# PCF8575_Shield.net
KiCad netlist of a schematic drawn in EAGLE
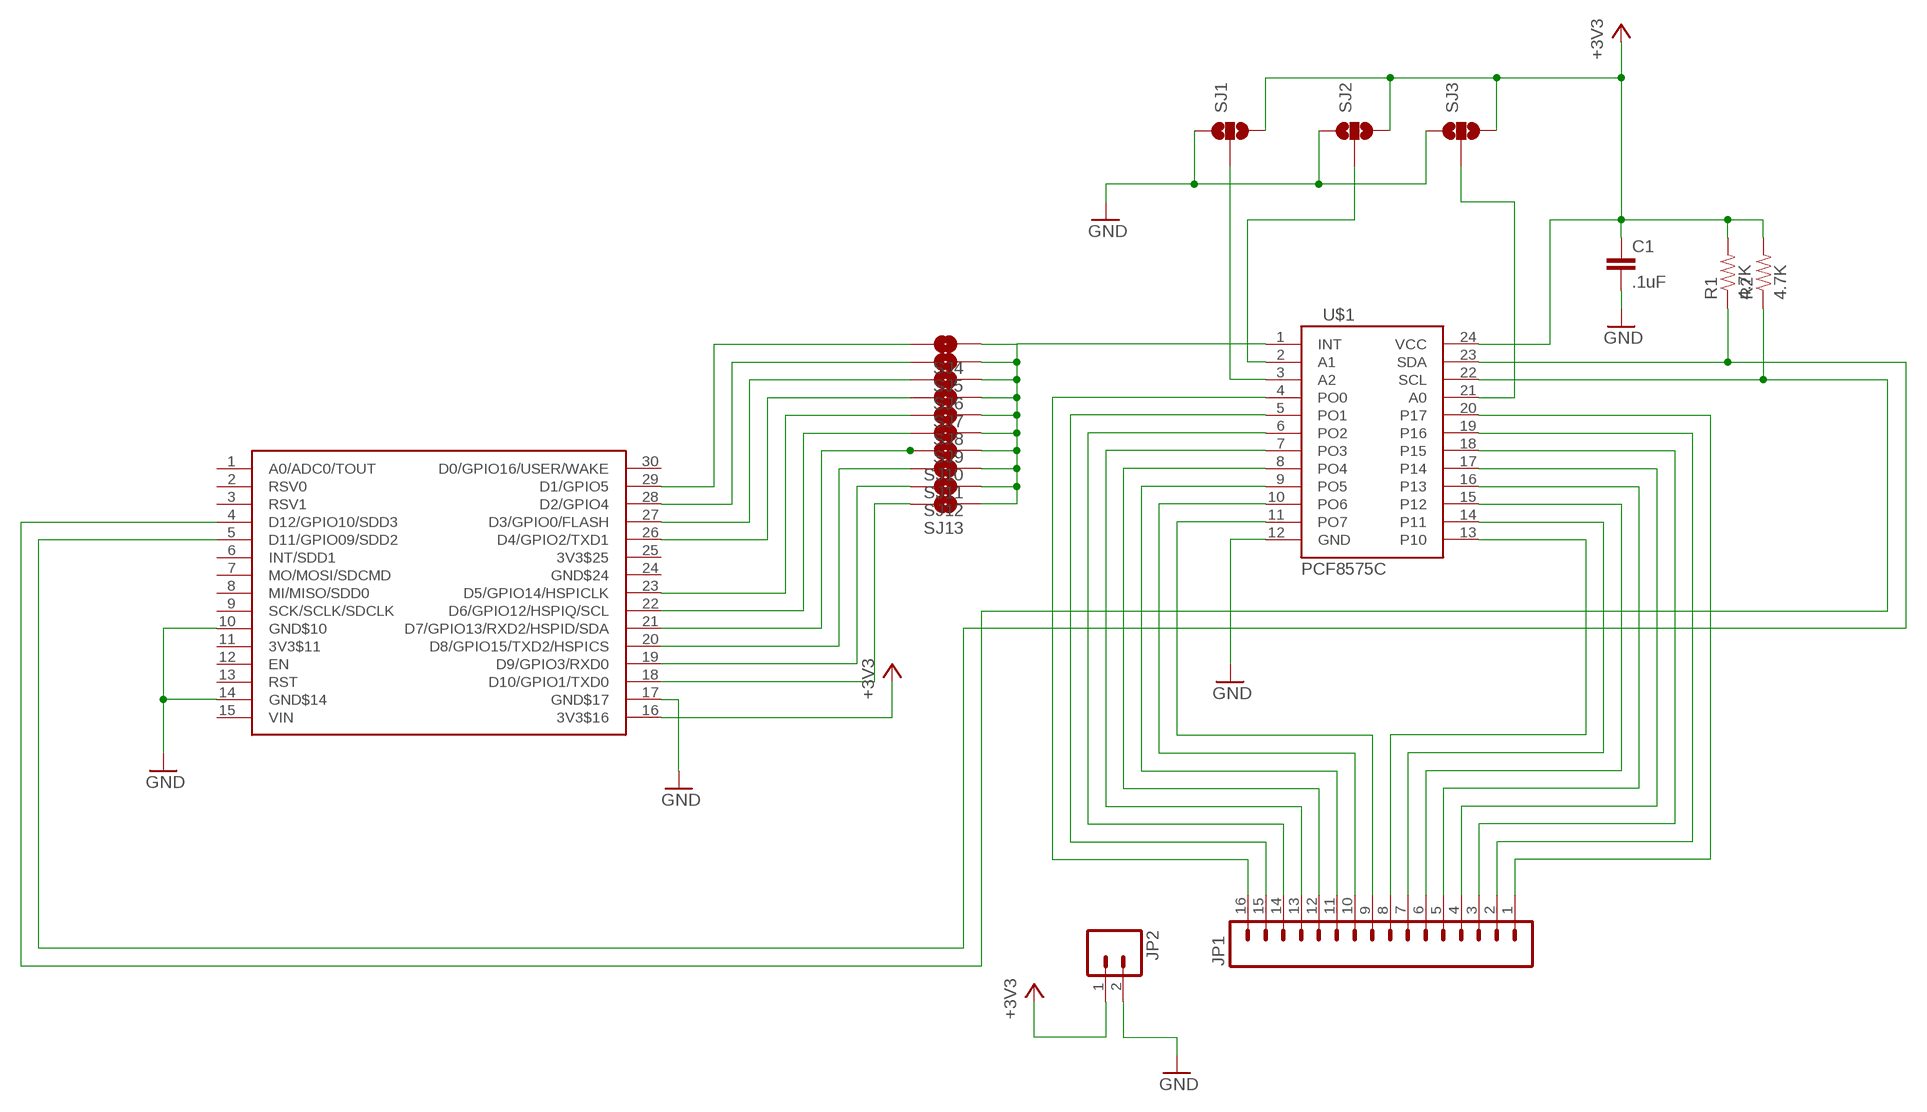
[diagram p0: schematic, sheet 1]

(export (version "E")
  (design (tool "Eeschema 10.0.6"))
  (components
    (comp (ref "C1")
      (value ".1uF")
      (footprint "eagle-import:0603-CAP")
      (libsource (lib "eagle-import") (part "CAP0603-CAP"))
    )
    (comp (ref "JP1")
      (value "M161X16_NO_SILK")
      (footprint "eagle-import:1X16_NO_SILK")
      (libsource (lib "eagle-import") (part "M161X16_NO_SILK"))
    )
    (comp (ref "JP2")
      (value "M02PTH")
      (footprint "eagle-import:1X02")
      (libsource (lib "eagle-import") (part "M02PTH"))
    )
    (comp (ref "R1")
      (value "4.7K")
      (footprint "eagle-import:0603-RES")
      (libsource (lib "eagle-import") (part "RESISTOR0603-RES"))
    )
    (comp (ref "R2")
      (value "4.7K")
      (footprint "eagle-import:0603-RES")
      (libsource (lib "eagle-import") (part "RESISTOR0603-RES"))
    )
    (comp (ref "SJ1")
      (value "SOLDERJUMPER_2WAYPASTE1&2")
      (footprint "eagle-import:SJ_3_PASTE1&2")
      (libsource (lib "eagle-import") (part "SOLDERJUMPER_2WAYPASTE1&2"))
    )
    (comp (ref "SJ2")
      (value "SOLDERJUMPER_2WAYPASTE1&2")
      (footprint "eagle-import:SJ_3_PASTE1&2")
      (libsource (lib "eagle-import") (part "SOLDERJUMPER_2WAYPASTE1&2"))
    )
    (comp (ref "SJ3")
      (value "SOLDERJUMPER_2WAYPASTE1&2")
      (footprint "eagle-import:SJ_3_PASTE1&2")
      (libsource (lib "eagle-import") (part "SOLDERJUMPER_2WAYPASTE1&2"))
    )
    (comp (ref "SJ4")
      (value "SOLDERJUMPERNO")
      (footprint "eagle-import:SJ_2S-NO")
      (libsource (lib "eagle-import") (part "SOLDERJUMPERNO"))
    )
    (comp (ref "SJ5")
      (value "SOLDERJUMPERNO")
      (footprint "eagle-import:SJ_2S-NO")
      (libsource (lib "eagle-import") (part "SOLDERJUMPERNO"))
    )
    (comp (ref "SJ6")
      (value "SOLDERJUMPERNO")
      (footprint "eagle-import:SJ_2S-NO")
      (libsource (lib "eagle-import") (part "SOLDERJUMPERNO"))
    )
    (comp (ref "SJ7")
      (value "SOLDERJUMPERNO")
      (footprint "eagle-import:SJ_2S-NO")
      (libsource (lib "eagle-import") (part "SOLDERJUMPERNO"))
    )
    (comp (ref "SJ8")
      (value "SOLDERJUMPERNO")
      (footprint "eagle-import:SJ_2S-NO")
      (libsource (lib "eagle-import") (part "SOLDERJUMPERNO"))
    )
    (comp (ref "SJ9")
      (value "SOLDERJUMPERNO")
      (footprint "eagle-import:SJ_2S-NO")
      (libsource (lib "eagle-import") (part "SOLDERJUMPERNO"))
    )
    (comp (ref "SJ10")
      (value "SOLDERJUMPERNO")
      (footprint "eagle-import:SJ_2S-NO")
      (libsource (lib "eagle-import") (part "SOLDERJUMPERNO"))
    )
    (comp (ref "SJ11")
      (value "SOLDERJUMPERNO")
      (footprint "eagle-import:SJ_2S-NO")
      (libsource (lib "eagle-import") (part "SOLDERJUMPERNO"))
    )
    (comp (ref "SJ12")
      (value "SOLDERJUMPERNO")
      (footprint "eagle-import:SJ_2S-NO")
      (libsource (lib "eagle-import") (part "SOLDERJUMPERNO"))
    )
    (comp (ref "SJ13")
      (value "SOLDERJUMPERNO")
      (footprint "eagle-import:SJ_2S-NO")
      (libsource (lib "eagle-import") (part "SOLDERJUMPERNO"))
    )
    (comp (ref "U$1")
      (value "PCF8575C")
      (footprint "eagle-import:SO-24DW")
      (libsource (lib "eagle-import") (part "PCF8575C"))
    )
    (comp (ref "U$2")
      (value "NERDSHIELD")
      (footprint "eagle-import:NERDUINO_STACK")
      (libsource (lib "eagle-import") (part "NERDSHIELD"))
    )
  )
  (nets
    (net (code "1") (name "+3V3") (class "Default")
      (node (ref "C1") (pin "1") (pinfunction "1_1") (pintype "passive"))
      (node (ref "JP2") (pin "1") (pinfunction "1_1") (pintype "passive"))
      (node (ref "R1") (pin "2") (pinfunction "2_2") (pintype "passive"))
      (node (ref "R2") (pin "2") (pinfunction "2_2") (pintype "passive"))
      (node (ref "SJ1") (pin "3") (pinfunction "3_3") (pintype "passive"))
      (node (ref "SJ2") (pin "3") (pinfunction "3_3") (pintype "passive"))
      (node (ref "SJ3") (pin "3") (pinfunction "3_3") (pintype "passive"))
      (node (ref "U$1") (pin "24") (pinfunction "VCC_24") (pintype "bidirectional"))
      (node (ref "U$2") (pin "16") (pinfunction "3V3$16_16") (pintype "bidirectional"))
    )
    (net (code "2") (name "GND") (class "Default")
      (node (ref "C1") (pin "2") (pinfunction "2_2") (pintype "passive"))
      (node (ref "JP2") (pin "2") (pinfunction "2_2") (pintype "passive"))
      (node (ref "SJ1") (pin "1") (pinfunction "1_1") (pintype "passive"))
      (node (ref "SJ2") (pin "1") (pinfunction "1_1") (pintype "passive"))
      (node (ref "SJ3") (pin "1") (pinfunction "1_1") (pintype "passive"))
      (node (ref "U$1") (pin "12") (pinfunction "GND_12") (pintype "bidirectional"))
      (node (ref "U$2") (pin "10") (pinfunction "GND$10_10") (pintype "bidirectional"))
      (node (ref "U$2") (pin "14") (pinfunction "GND$14_14") (pintype "bidirectional"))
      (node (ref "U$2") (pin "17") (pinfunction "GND$17_17") (pintype "bidirectional"))
    )
    (net (code "3") (name "Net-(U$1-A0)") (class "Default")
      (node (ref "SJ3") (pin "2") (pinfunction "2_2") (pintype "passive"))
      (node (ref "U$1") (pin "21") (pinfunction "A0_21") (pintype "bidirectional"))
    )
    (net (code "4") (name "Net-(U$1-A1)") (class "Default")
      (node (ref "SJ2") (pin "2") (pinfunction "2_2") (pintype "passive"))
      (node (ref "U$1") (pin "2") (pinfunction "A1_2") (pintype "bidirectional"))
    )
    (net (code "5") (name "Net-(U$1-A2)") (class "Default")
      (node (ref "SJ1") (pin "2") (pinfunction "2_2") (pintype "passive"))
      (node (ref "U$1") (pin "3") (pinfunction "A2_3") (pintype "bidirectional"))
    )
    (net (code "6") (name "Net-(U$1-INT)") (class "Default")
      (node (ref "SJ10") (pin "1") (pinfunction "1_1") (pintype "passive"))
      (node (ref "SJ11") (pin "1") (pinfunction "1_1") (pintype "passive"))
      (node (ref "SJ12") (pin "1") (pinfunction "1_1") (pintype "passive"))
      (node (ref "SJ13") (pin "1") (pinfunction "1_1") (pintype "passive"))
      (node (ref "SJ4") (pin "1") (pinfunction "1_1") (pintype "passive"))
      (node (ref "SJ5") (pin "1") (pinfunction "1_1") (pintype "passive"))
      (node (ref "SJ6") (pin "1") (pinfunction "1_1") (pintype "passive"))
      (node (ref "SJ7") (pin "1") (pinfunction "1_1") (pintype "passive"))
      (node (ref "SJ8") (pin "1") (pinfunction "1_1") (pintype "passive"))
      (node (ref "SJ9") (pin "1") (pinfunction "1_1") (pintype "passive"))
      (node (ref "U$1") (pin "1") (pinfunction "INT_1") (pintype "bidirectional"))
    )
    (net (code "7") (name "Net-(U$1-P10)") (class "Default")
      (node (ref "JP1") (pin "8") (pinfunction "8_8") (pintype "passive"))
      (node (ref "U$1") (pin "13") (pinfunction "P10_13") (pintype "bidirectional"))
    )
    (net (code "8") (name "Net-(U$1-P11)") (class "Default")
      (node (ref "JP1") (pin "7") (pinfunction "7_7") (pintype "passive"))
      (node (ref "U$1") (pin "14") (pinfunction "P11_14") (pintype "bidirectional"))
    )
    (net (code "9") (name "Net-(U$1-P12)") (class "Default")
      (node (ref "JP1") (pin "6") (pinfunction "6_6") (pintype "passive"))
      (node (ref "U$1") (pin "15") (pinfunction "P12_15") (pintype "bidirectional"))
    )
    (net (code "10") (name "Net-(U$1-P13)") (class "Default")
      (node (ref "JP1") (pin "5") (pinfunction "5_5") (pintype "passive"))
      (node (ref "U$1") (pin "16") (pinfunction "P13_16") (pintype "bidirectional"))
    )
    (net (code "11") (name "Net-(U$1-P14)") (class "Default")
      (node (ref "JP1") (pin "4") (pinfunction "4_4") (pintype "passive"))
      (node (ref "U$1") (pin "17") (pinfunction "P14_17") (pintype "bidirectional"))
    )
    (net (code "12") (name "Net-(U$1-P15)") (class "Default")
      (node (ref "JP1") (pin "3") (pinfunction "3_3") (pintype "passive"))
      (node (ref "U$1") (pin "18") (pinfunction "P15_18") (pintype "bidirectional"))
    )
    (net (code "13") (name "Net-(U$1-P16)") (class "Default")
      (node (ref "JP1") (pin "2") (pinfunction "2_2") (pintype "passive"))
      (node (ref "U$1") (pin "19") (pinfunction "P16_19") (pintype "bidirectional"))
    )
    (net (code "14") (name "Net-(U$1-P17)") (class "Default")
      (node (ref "JP1") (pin "1") (pinfunction "1_1") (pintype "passive"))
      (node (ref "U$1") (pin "20") (pinfunction "P17_20") (pintype "bidirectional"))
    )
    (net (code "15") (name "Net-(U$1-PO0)") (class "Default")
      (node (ref "JP1") (pin "16") (pinfunction "16_16") (pintype "passive"))
      (node (ref "U$1") (pin "4") (pinfunction "PO0_4") (pintype "bidirectional"))
    )
    (net (code "16") (name "Net-(U$1-PO1)") (class "Default")
      (node (ref "JP1") (pin "15") (pinfunction "15_15") (pintype "passive"))
      (node (ref "U$1") (pin "5") (pinfunction "PO1_5") (pintype "bidirectional"))
    )
    (net (code "17") (name "Net-(U$1-PO2)") (class "Default")
      (node (ref "JP1") (pin "14") (pinfunction "14_14") (pintype "passive"))
      (node (ref "U$1") (pin "6") (pinfunction "PO2_6") (pintype "bidirectional"))
    )
    (net (code "18") (name "Net-(U$1-PO3)") (class "Default")
      (node (ref "JP1") (pin "13") (pinfunction "13_13") (pintype "passive"))
      (node (ref "U$1") (pin "7") (pinfunction "PO3_7") (pintype "bidirectional"))
    )
    (net (code "19") (name "Net-(U$1-PO4)") (class "Default")
      (node (ref "JP1") (pin "12") (pinfunction "12_12") (pintype "passive"))
      (node (ref "U$1") (pin "8") (pinfunction "PO4_8") (pintype "bidirectional"))
    )
    (net (code "20") (name "Net-(U$1-PO5)") (class "Default")
      (node (ref "JP1") (pin "11") (pinfunction "11_11") (pintype "passive"))
      (node (ref "U$1") (pin "9") (pinfunction "PO5_9") (pintype "bidirectional"))
    )
    (net (code "21") (name "Net-(U$1-PO6)") (class "Default")
      (node (ref "JP1") (pin "10") (pinfunction "10_10") (pintype "passive"))
      (node (ref "U$1") (pin "10") (pinfunction "PO6_10") (pintype "bidirectional"))
    )
    (net (code "22") (name "Net-(U$1-PO7)") (class "Default")
      (node (ref "JP1") (pin "9") (pinfunction "9_9") (pintype "passive"))
      (node (ref "U$1") (pin "11") (pinfunction "PO7_11") (pintype "bidirectional"))
    )
    (net (code "23") (name "Net-(U$1-SCL)") (class "Default")
      (node (ref "R2") (pin "1") (pinfunction "1_1") (pintype "passive"))
      (node (ref "U$1") (pin "22") (pinfunction "SCL_22") (pintype "bidirectional"))
      (node (ref "U$2") (pin "4") (pinfunction "D12/GPIO10/SDD3_4") (pintype "bidirectional"))
    )
    (net (code "24") (name "Net-(U$1-SDA)") (class "Default")
      (node (ref "R1") (pin "1") (pinfunction "1_1") (pintype "passive"))
      (node (ref "U$1") (pin "23") (pinfunction "SDA_23") (pintype "bidirectional"))
      (node (ref "U$2") (pin "5") (pinfunction "D11/GPIO09/SDD2_5") (pintype "bidirectional"))
    )
    (net (code "25") (name "Net-(U$2-D1{slash}GPIO5)") (class "Default")
      (node (ref "SJ4") (pin "2") (pinfunction "2_2") (pintype "passive"))
      (node (ref "U$2") (pin "29") (pinfunction "D1/GPIO5_29") (pintype "bidirectional"))
    )
    (net (code "26") (name "Net-(U$2-D2{slash}GPIO4)") (class "Default")
      (node (ref "SJ5") (pin "2") (pinfunction "2_2") (pintype "passive"))
      (node (ref "U$2") (pin "28") (pinfunction "D2/GPIO4_28") (pintype "bidirectional"))
    )
    (net (code "27") (name "Net-(U$2-D3{slash}GPIO0{slash}FLASH)") (class "Default")
      (node (ref "SJ6") (pin "2") (pinfunction "2_2") (pintype "passive"))
      (node (ref "U$2") (pin "27") (pinfunction "D3/GPIO0/FLASH_27") (pintype "bidirectional"))
    )
    (net (code "28") (name "Net-(U$2-D4{slash}GPIO2{slash}TXD1)") (class "Default")
      (node (ref "SJ7") (pin "2") (pinfunction "2_2") (pintype "passive"))
      (node (ref "U$2") (pin "26") (pinfunction "D4/GPIO2/TXD1_26") (pintype "bidirectional"))
    )
    (net (code "29") (name "Net-(U$2-D5{slash}GPIO14{slash}HSPICLK)") (class "Default")
      (node (ref "SJ8") (pin "2") (pinfunction "2_2") (pintype "passive"))
      (node (ref "U$2") (pin "23") (pinfunction "D5/GPIO14/HSPICLK_23") (pintype "bidirectional"))
    )
    (net (code "30") (name "Net-(U$2-D6{slash}GPIO12{slash}HSPIQ{slash}SCL)") (class "Default")
      (node (ref "SJ9") (pin "2") (pinfunction "2_2") (pintype "passive"))
      (node (ref "U$2") (pin "22") (pinfunction "D6/GPIO12/HSPIQ/SCL_22") (pintype "bidirectional"))
    )
    (net (code "31") (name "Net-(U$2-D7{slash}GPIO13{slash}RXD2{slash}HSPID{slash}SDA)") (class "Default")
      (node (ref "SJ10") (pin "2") (pinfunction "2_2") (pintype "passive"))
      (node (ref "U$2") (pin "21") (pinfunction "D7/GPIO13/RXD2/HSPID/SDA_21") (pintype "bidirectional"))
    )
    (net (code "32") (name "Net-(U$2-D8{slash}GPIO15{slash}TXD2{slash}HSPICS)") (class "Default")
      (node (ref "SJ11") (pin "2") (pinfunction "2_2") (pintype "passive"))
      (node (ref "U$2") (pin "20") (pinfunction "D8/GPIO15/TXD2/HSPICS_20") (pintype "bidirectional"))
    )
    (net (code "33") (name "Net-(U$2-D9{slash}GPIO3{slash}RXD0)") (class "Default")
      (node (ref "SJ12") (pin "2") (pinfunction "2_2") (pintype "passive"))
      (node (ref "U$2") (pin "19") (pinfunction "D9/GPIO3/RXD0_19") (pintype "bidirectional"))
    )
    (net (code "34") (name "Net-(U$2-D10{slash}GPIO1{slash}TXD0)") (class "Default")
      (node (ref "SJ13") (pin "2") (pinfunction "2_2") (pintype "passive"))
      (node (ref "U$2") (pin "18") (pinfunction "D10/GPIO1/TXD0_18") (pintype "bidirectional"))
    )
    (net (code "35") (name "unconnected-(U$2-3V3$11-Pad11)") (class "Default")
      (node (ref "U$2") (pin "11") (pinfunction "3V3$11_11") (pintype "bidirectional"))
    )
    (net (code "36") (name "unconnected-(U$2-3V3$25-Pad25)") (class "Default")
      (node (ref "U$2") (pin "25") (pinfunction "3V3$25_25") (pintype "bidirectional"))
    )
    (net (code "37") (name "unconnected-(U$2-A0{slash}ADC0{slash}TOUT-Pad1)") (class "Default")
      (node (ref "U$2") (pin "1") (pinfunction "A0/ADC0/TOUT_1") (pintype "bidirectional"))
    )
    (net (code "38") (name "unconnected-(U$2-D0{slash}GPIO16{slash}USER{slash}WAKE-Pad30)") (class "Default")
      (node (ref "U$2") (pin "30") (pinfunction "D0/GPIO16/USER/WAKE_30") (pintype "bidirectional"))
    )
    (net (code "39") (name "unconnected-(U$2-EN-Pad12)") (class "Default")
      (node (ref "U$2") (pin "12") (pinfunction "EN_12") (pintype "bidirectional"))
    )
    (net (code "40") (name "unconnected-(U$2-GND$24-Pad24)") (class "Default")
      (node (ref "U$2") (pin "24") (pinfunction "GND$24_24") (pintype "bidirectional"))
    )
    (net (code "41") (name "unconnected-(U$2-INT{slash}SDD1-Pad6)") (class "Default")
      (node (ref "U$2") (pin "6") (pinfunction "INT/SDD1_6") (pintype "bidirectional"))
    )
    (net (code "42") (name "unconnected-(U$2-MI{slash}MISO{slash}SDD0-Pad8)") (class "Default")
      (node (ref "U$2") (pin "8") (pinfunction "MI/MISO/SDD0_8") (pintype "bidirectional"))
    )
    (net (code "43") (name "unconnected-(U$2-MO{slash}MOSI{slash}SDCMD-Pad7)") (class "Default")
      (node (ref "U$2") (pin "7") (pinfunction "MO/MOSI/SDCMD_7") (pintype "bidirectional"))
    )
    (net (code "44") (name "unconnected-(U$2-RST-Pad13)") (class "Default")
      (node (ref "U$2") (pin "13") (pinfunction "RST_13") (pintype "bidirectional"))
    )
    (net (code "45") (name "unconnected-(U$2-RSV0-Pad2)") (class "Default")
      (node (ref "U$2") (pin "2") (pinfunction "RSV0_2") (pintype "bidirectional"))
    )
    (net (code "46") (name "unconnected-(U$2-RSV1-Pad3)") (class "Default")
      (node (ref "U$2") (pin "3") (pinfunction "RSV1_3") (pintype "bidirectional"))
    )
    (net (code "47") (name "unconnected-(U$2-SCK{slash}SCLK{slash}SDCLK-Pad9)") (class "Default")
      (node (ref "U$2") (pin "9") (pinfunction "SCK/SCLK/SDCLK_9") (pintype "bidirectional"))
    )
    (net (code "48") (name "unconnected-(U$2-VIN-Pad15)") (class "Default")
      (node (ref "U$2") (pin "15") (pinfunction "VIN_15") (pintype "bidirectional"))
    )
  )
)
